# adc_mcp3913.net
KiCad netlist of a schematic drawn in Altium Designer
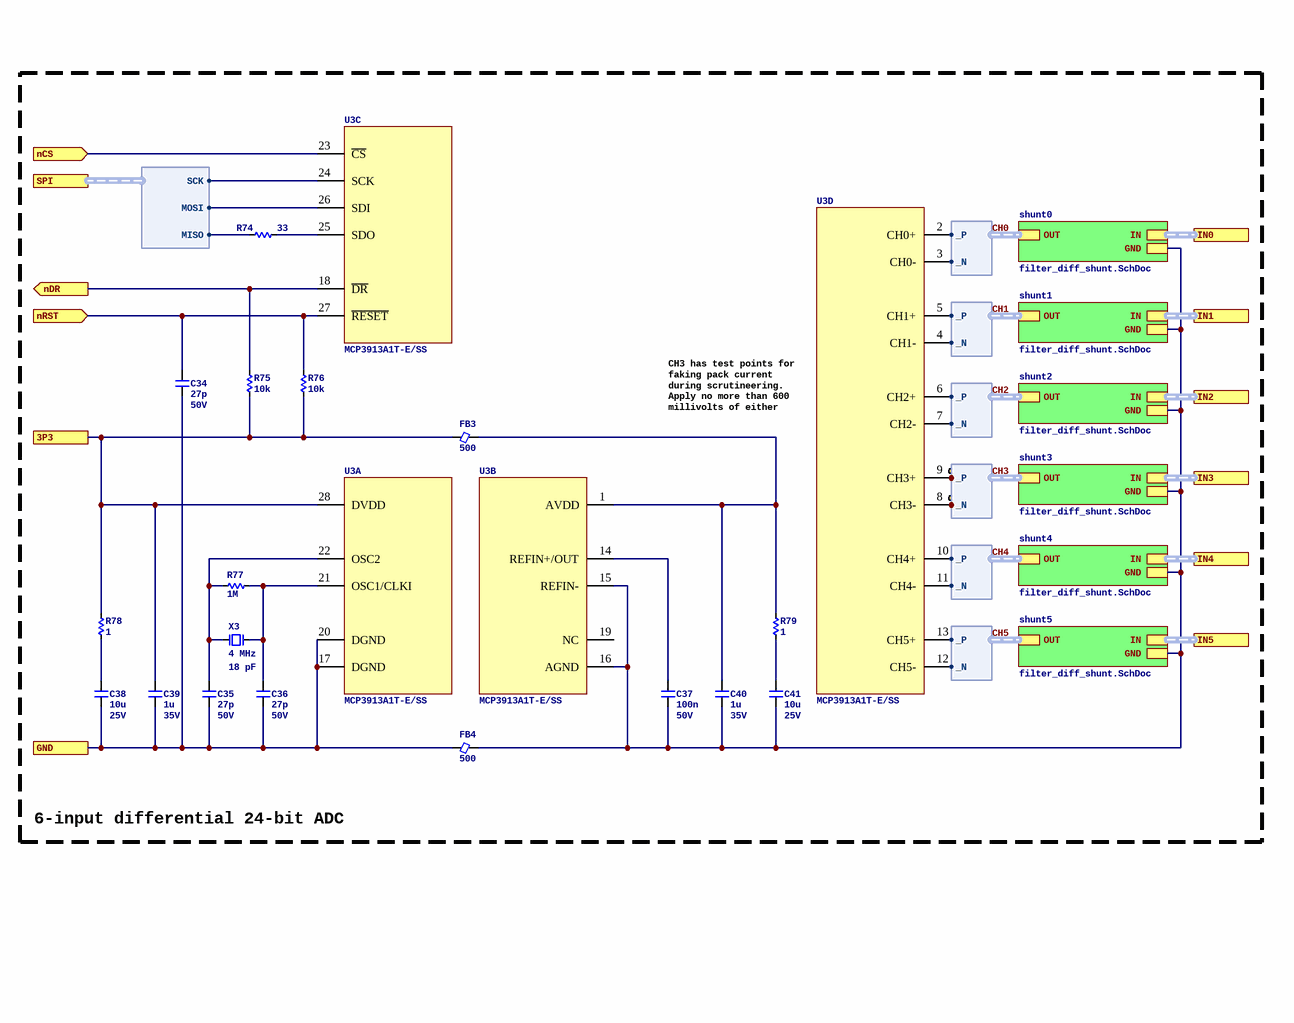
[diagram p0: adc_mcp3913.SchDoc]

(export (version "E")
  (design (tool "Eeschema 10.0.6"))
  (components
    (comp (ref "C34")
      (value "0402CG270J500NT")
      (footprint "C0402")
      (fields
        (field (name "CAPACITANCE") "27p")
        (field (name "MANUFACTURER") "FH(Guangdong Fenghua Advanced Tech)")
        (field (name "VOLTAGE RATING") "50V")
      )
      (libsource (lib "database") (part "__template_cap"))
    )
    (comp (ref "C35")
      (value "0402CG270J500NT")
      (footprint "C0402")
      (fields
        (field (name "CAPACITANCE") "27p")
        (field (name "MANUFACTURER") "FH(Guangdong Fenghua Advanced Tech)")
        (field (name "VOLTAGE RATING") "50V")
      )
      (libsource (lib "database") (part "__template_cap"))
    )
    (comp (ref "C36")
      (value "0402CG270J500NT")
      (footprint "C0402")
      (fields
        (field (name "CAPACITANCE") "27p")
        (field (name "MANUFACTURER") "FH(Guangdong Fenghua Advanced Tech)")
        (field (name "VOLTAGE RATING") "50V")
      )
      (libsource (lib "database") (part "__template_cap"))
    )
    (comp (ref "C37")
      (value "CL05B104KB54PNC")
      (footprint "C0402")
      (fields
        (field (name "CAPACITANCE") "100n")
        (field (name "MANUFACTURER") "Samsung Electro-Mechanics")
        (field (name "VOLTAGE RATING") "50V")
      )
      (libsource (lib "database") (part "__template_cap"))
    )
    (comp (ref "C38")
      (value "CL21B106KAYQNNE")
      (footprint "C0805")
      (fields
        (field (name "CAPACITANCE") "10u")
        (field (name "MANUFACTURER") "Samsung Electro-Mechanics")
        (field (name "VOLTAGE RATING") "25V")
      )
      (libsource (lib "database") (part "__template_cap"))
    )
    (comp (ref "C39")
      (value "GMK107AB7105KAHT")
      (footprint "C0603")
      (fields
        (field (name "CAPACITANCE") "1u")
        (field (name "MANUFACTURER") "Taiyo Yuden")
        (field (name "VOLTAGE RATING") "35V")
      )
      (libsource (lib "database") (part "__template_cap"))
    )
    (comp (ref "C40")
      (value "GMK107AB7105KAHT")
      (footprint "C0603")
      (fields
        (field (name "CAPACITANCE") "1u")
        (field (name "MANUFACTURER") "Taiyo Yuden")
        (field (name "VOLTAGE RATING") "35V")
      )
      (libsource (lib "database") (part "__template_cap"))
    )
    (comp (ref "C41")
      (value "CL21B106KAYQNNE")
      (footprint "C0805")
      (fields
        (field (name "CAPACITANCE") "10u")
        (field (name "MANUFACTURER") "Samsung Electro-Mechanics")
        (field (name "VOLTAGE RATING") "25V")
      )
      (libsource (lib "database") (part "__template_cap"))
    )
    (comp (ref "FB3")
      (value "BLM15AX601SN1D")
      (footprint "FB0402")
      (fields (field (name "MANUFACTURER") "Murata Electronics") (field (name "CURRENT RATING (MA)") "500"))
      (libsource (lib "database") (part "__template_fb"))
    )
    (comp (ref "FB4")
      (value "BLM15AX601SN1D")
      (footprint "FB0402")
      (fields (field (name "MANUFACTURER") "Murata Electronics") (field (name "CURRENT RATING (MA)") "500"))
      (libsource (lib "database") (part "__template_fb"))
    )
    (comp (ref "R74")
      (value "33")
      (footprint "R0402")
      (fields
        (field (name "TOLERANCE") "1%")
        (field (name "MANUFACTURER PART NUMBER") "0402WGF330JTCE")
        (field (name "MANUFACTURER") "UNI-ROYAL(Uniroyal Elec)")
      )
      (libsource (lib "database") (part "__template_resistor"))
    )
    (comp (ref "R75")
      (value "10k")
      (footprint "R0402")
      (fields
        (field (name "TOLERANCE") "1%")
        (field (name "MANUFACTURER PART NUMBER") "0402WGF1002TCE")
        (field (name "MANUFACTURER") "UNI-ROYAL(Uniroyal Elec)")
      )
      (libsource (lib "database") (part "__template_resistor"))
    )
    (comp (ref "R76")
      (value "10k")
      (footprint "R0402")
      (fields
        (field (name "TOLERANCE") "1%")
        (field (name "MANUFACTURER PART NUMBER") "0402WGF1002TCE")
        (field (name "MANUFACTURER") "UNI-ROYAL(Uniroyal Elec)")
      )
      (libsource (lib "database") (part "__template_resistor"))
    )
    (comp (ref "R77")
      (value "1M")
      (footprint "R0402")
      (fields
        (field (name "TOLERANCE") "1%")
        (field (name "MANUFACTURER PART NUMBER") "0402WGF1004TCE")
        (field (name "MANUFACTURER") "UNI-ROYAL(Uniroyal Elec)")
      )
      (libsource (lib "database") (part "__template_resistor"))
    )
    (comp (ref "R78")
      (value "1")
      (footprint "R0402")
      (fields
        (field (name "TOLERANCE") "1%")
        (field (name "MANUFACTURER PART NUMBER") "CRCW04021R00FKED")
        (field (name "MANUFACTURER") "Vishay Intertech")
      )
      (libsource (lib "database") (part "__template_resistor"))
    )
    (comp (ref "R79")
      (value "1")
      (footprint "R0402")
      (fields
        (field (name "TOLERANCE") "1%")
        (field (name "MANUFACTURER PART NUMBER") "CRCW04021R00FKED")
        (field (name "MANUFACTURER") "Vishay Intertech")
      )
      (libsource (lib "database") (part "__template_resistor"))
    )
    (comp (ref "TP71")
      (value "RH-5000")
      (footprint "TP_RH-5000")
      (fields (field (name "MANUFACTURER") "ronghe"))
      (libsource (lib "database") (part "__template_testpoint"))
    )
    (comp (ref "TP72")
      (value "RH-5001")
      (footprint "TP_RH-5001")
      (fields (field (name "MANUFACTURER") "ronghe"))
      (libsource (lib "database") (part "__template_testpoint"))
    )
    (comp (ref "U3")
      (value "MCP3913A1T-E/SS")
      (footprint "28SSOP65")
      (description "Analog Circuit, 1 Func, PDSO28")
      (fields (field (name "MANUFACTURER") "Microchip"))
      (libsource (lib "") (part "ADC_MCP3913A1T-E/SS_1"))
    )
    (comp (ref "X3")
      (value "ABLS2-4.000MHZ-D4Y-T")
      (footprint "XTAL_HC49US_SMD")
      (description "CRYSTAL 4.000 MHZ 18PF SMD")
      (fields
        (field (name "MANUFACTURER") "Abracon LLC")
        (field (name "FREQUENCY") "4 MHz")
        (field (name "LOAD CAPACITANCE") "18 pF")
      )
      (libsource (lib "SSCP") (part "XTAL_ABLS2-4.000MHZ-D4Y-T"))
    )
  )
  (nets
    (net (code "14") (name "/3P3") (class "Default")
      (node (ref "C39") (pin "1") (pintype "passive"))
      (node (ref "FB3") (pin "1") (pintype "passive"))
      (node (ref "R75") (pin "2") (pintype "passive"))
      (node (ref "R76") (pin "2") (pintype "passive"))
      (node (ref "R78") (pin "2") (pintype "passive"))
      (node (ref "U3") (pin "28") (pinfunction "DVDD_28") (pintype "passive"))
    )
    (net (code "21") (name "/GND") (class "Default")
      (node (ref "C34") (pin "2") (pintype "passive"))
      (node (ref "C35") (pin "2") (pintype "passive"))
      (node (ref "C36") (pin "2") (pintype "passive"))
      (node (ref "C38") (pin "2") (pintype "passive"))
      (node (ref "C39") (pin "2") (pintype "passive"))
      (node (ref "FB4") (pin "1") (pintype "passive"))
      (node (ref "U3") (pin "17") (pinfunction "DGND_17") (pintype "passive"))
      (node (ref "U3") (pin "20") (pinfunction "DGND_20") (pintype "passive"))
    )
    (net (code "22") (name "/GND_1") (class "Default")
      (node (ref "C37") (pin "2") (pintype "passive"))
      (node (ref "C40") (pin "2") (pintype "passive"))
      (node (ref "C41") (pin "2") (pintype "passive"))
      (node (ref "FB4") (pin "2") (pintype "passive"))
      (node (ref "U3") (pin "15") (pinfunction "REFIN-_15") (pintype "passive"))
      (node (ref "U3") (pin "16") (pinfunction "AGND_16") (pintype "passive"))
    )
    (net (code "29") (name "/MISO") (class "Default") (node (ref "R74") (pin "2") (pintype "passive")))
    (net (code "30") (name "/MOSI") (class "Default")
      (node (ref "U3") (pin "26") (pinfunction "SDI_26") (pintype "passive"))
    )
    (net (code "31") (name "/SCK") (class "Default")
      (node (ref "U3") (pin "24") (pinfunction "SCK_24") (pintype "passive"))
    )
    (net (code "32") (name "/nCS") (class "Default")
      (node (ref "U3") (pin "23") (pinfunction "~{CS}_23") (pintype "passive"))
    )
    (net (code "33") (name "/nDR") (class "Default")
      (node (ref "R75") (pin "1") (pintype "passive"))
      (node (ref "U3") (pin "18") (pinfunction "~{DR}_18") (pintype "passive"))
    )
    (net (code "34") (name "/nRST") (class "Default")
      (node (ref "C34") (pin "1") (pintype "passive"))
      (node (ref "R76") (pin "1") (pintype "passive"))
      (node (ref "U3") (pin "27") (pinfunction "~{RESET}_27") (pintype "passive"))
    )
    (net (code "36") (name "Net-(C38-Pad1)") (class "Default")
      (node (ref "C38") (pin "1") (pintype "passive"))
      (node (ref "R78") (pin "1") (pintype "passive"))
    )
    (net (code "37") (name "Net-(C41-Pad1)") (class "Default")
      (node (ref "C41") (pin "1") (pintype "passive"))
      (node (ref "R79") (pin "1") (pintype "passive"))
    )
    (net (code "38") (name "Net-(U3A-OSC1{slash}CLKI)") (class "Default")
      (node (ref "C36") (pin "1") (pintype "passive"))
      (node (ref "R77") (pin "1") (pintype "passive"))
      (node (ref "U3") (pin "21") (pinfunction "OSC1/CLKI_21") (pintype "passive"))
      (node (ref "X3") (pin "1") (pinfunction "1_1") (pintype "passive"))
    )
    (net (code "39") (name "Net-(U3A-OSC2)") (class "Default")
      (node (ref "C35") (pin "1") (pintype "passive"))
      (node (ref "R77") (pin "2") (pintype "passive"))
      (node (ref "U3") (pin "22") (pinfunction "OSC2_22") (pintype "passive"))
      (node (ref "X3") (pin "2") (pinfunction "2_2") (pintype "passive"))
    )
    (net (code "40") (name "Net-(U3B-AVDD)") (class "Default")
      (node (ref "C40") (pin "1") (pintype "passive"))
      (node (ref "FB3") (pin "2") (pintype "passive"))
      (node (ref "R79") (pin "2") (pintype "passive"))
      (node (ref "U3") (pin "1") (pinfunction "AVDD_1") (pintype "passive"))
    )
    (net (code "41") (name "Net-(U3B-REFIN+{slash}OUT)") (class "Default")
      (node (ref "C37") (pin "1") (pintype "passive"))
      (node (ref "U3") (pin "14") (pinfunction "REFIN+/OUT_14") (pintype "passive"))
    )
    (net (code "42") (name "Net-(U3C-SDO)") (class "Default")
      (node (ref "R74") (pin "1") (pintype "passive"))
      (node (ref "U3") (pin "25") (pinfunction "SDO_25") (pintype "passive"))
    )
    (net (code "43") (name "Net-(U3D-CH3+)") (class "Default")
      (node (ref "TP71") (pin "1") (pintype "passive"))
      (node (ref "U3") (pin "9") (pinfunction "CH3+_9") (pintype "passive"))
    )
    (net (code "44") (name "Net-(U3D-CH3-)") (class "Default")
      (node (ref "TP72") (pin "1") (pintype "passive"))
      (node (ref "U3") (pin "8") (pinfunction "CH3-_8") (pintype "passive"))
    )
    (net (code "45") (name "unconnected-(U3B-NC-Pad19)") (class "Default")
      (node (ref "U3") (pin "19") (pinfunction "NC_19") (pintype "passive"))
    )
    (net (code "46") (name "unconnected-(U3D-CH0+-Pad2)") (class "Default")
      (node (ref "U3") (pin "2") (pinfunction "CH0+_2") (pintype "passive"))
    )
    (net (code "47") (name "unconnected-(U3D-CH0--Pad3)") (class "Default")
      (node (ref "U3") (pin "3") (pinfunction "CH0-_3") (pintype "passive"))
    )
    (net (code "48") (name "unconnected-(U3D-CH1+-Pad5)") (class "Default")
      (node (ref "U3") (pin "5") (pinfunction "CH1+_5") (pintype "passive"))
    )
    (net (code "49") (name "unconnected-(U3D-CH1--Pad4)") (class "Default")
      (node (ref "U3") (pin "4") (pinfunction "CH1-_4") (pintype "passive"))
    )
    (net (code "50") (name "unconnected-(U3D-CH2+-Pad6)") (class "Default")
      (node (ref "U3") (pin "6") (pinfunction "CH2+_6") (pintype "passive"))
    )
    (net (code "51") (name "unconnected-(U3D-CH2--Pad7)") (class "Default")
      (node (ref "U3") (pin "7") (pinfunction "CH2-_7") (pintype "passive"))
    )
    (net (code "52") (name "unconnected-(U3D-CH4+-Pad10)") (class "Default")
      (node (ref "U3") (pin "10") (pinfunction "CH4+_10") (pintype "passive"))
    )
    (net (code "53") (name "unconnected-(U3D-CH4--Pad11)") (class "Default")
      (node (ref "U3") (pin "11") (pinfunction "CH4-_11") (pintype "passive"))
    )
    (net (code "54") (name "unconnected-(U3D-CH5+-Pad13)") (class "Default")
      (node (ref "U3") (pin "13") (pinfunction "CH5+_13") (pintype "passive"))
    )
    (net (code "55") (name "unconnected-(U3D-CH5--Pad12)") (class "Default")
      (node (ref "U3") (pin "12") (pinfunction "CH5-_12") (pintype "passive"))
    )
  )
)
